# W023X.net
KiCad netlist of a schematic drawn in EAGLE
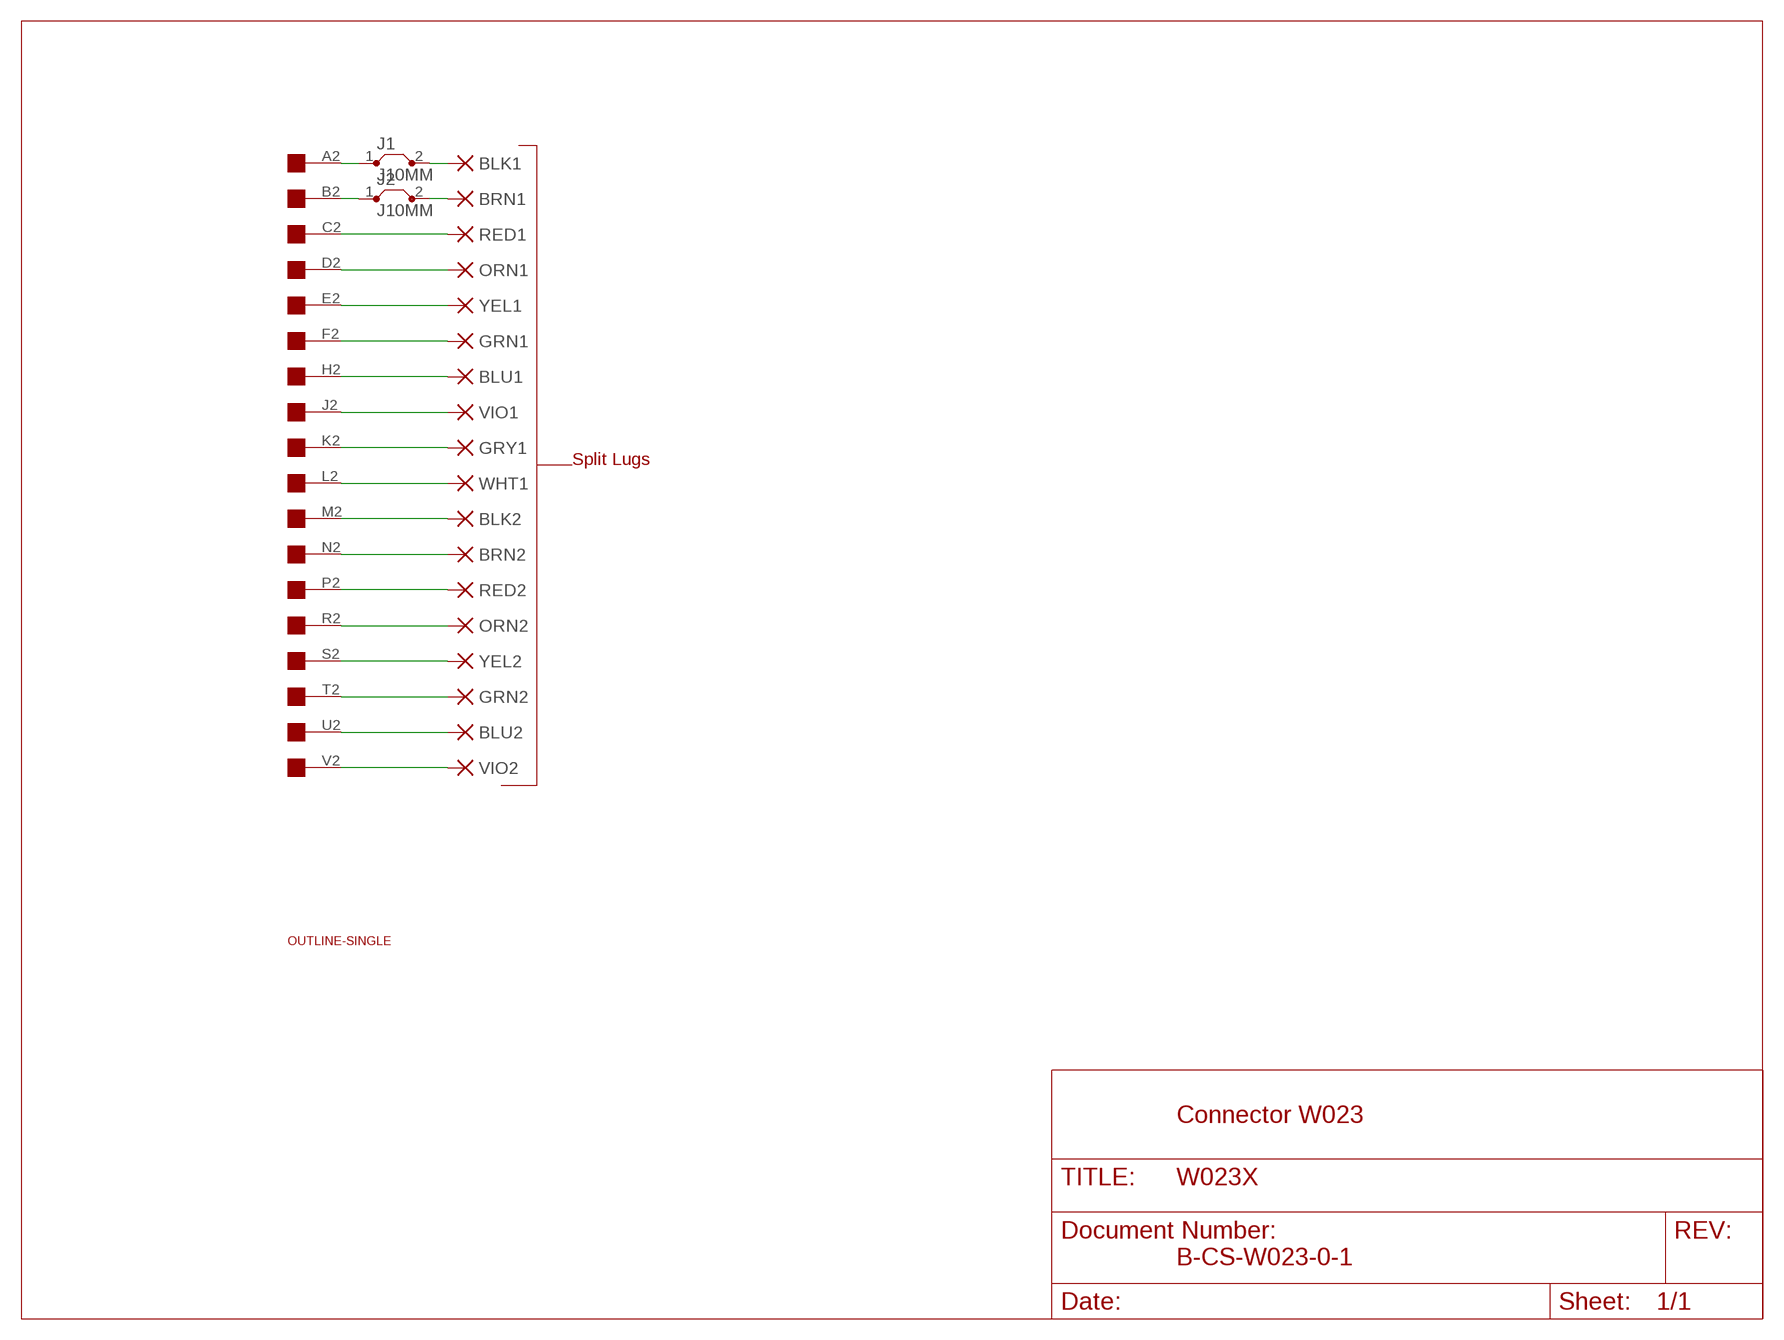
[diagram p0: schematic, sheet 1]

(export (version "E")
  (design (tool "Eeschema 10.0.6"))
  (components
    (comp (ref "BLK1")
      (value "PAD-0465")
      (footprint "eagle-import:0465")
      (libsource (lib "eagle-import") (part "PAD-0465"))
    )
    (comp (ref "BLK2")
      (value "PAD-0465")
      (footprint "eagle-import:0465")
      (libsource (lib "eagle-import") (part "PAD-0465"))
    )
    (comp (ref "BLU1")
      (value "PAD-0465")
      (footprint "eagle-import:0465")
      (libsource (lib "eagle-import") (part "PAD-0465"))
    )
    (comp (ref "BLU2")
      (value "PAD-0465")
      (footprint "eagle-import:0465")
      (libsource (lib "eagle-import") (part "PAD-0465"))
    )
    (comp (ref "BRN1")
      (value "PAD-0465")
      (footprint "eagle-import:0465")
      (libsource (lib "eagle-import") (part "PAD-0465"))
    )
    (comp (ref "BRN2")
      (value "PAD-0465")
      (footprint "eagle-import:0465")
      (libsource (lib "eagle-import") (part "PAD-0465"))
    )
    (comp (ref "GRN1")
      (value "PAD-0465")
      (footprint "eagle-import:0465")
      (libsource (lib "eagle-import") (part "PAD-0465"))
    )
    (comp (ref "GRN2")
      (value "PAD-0465")
      (footprint "eagle-import:0465")
      (libsource (lib "eagle-import") (part "PAD-0465"))
    )
    (comp (ref "GRY1")
      (value "PAD-0465")
      (footprint "eagle-import:0465")
      (libsource (lib "eagle-import") (part "PAD-0465"))
    )
    (comp (ref "J1")
      (value "J10MM")
      (footprint "eagle-import:10")
      (libsource (lib "eagle-import") (part "J10MM"))
    )
    (comp (ref "J2")
      (value "J10MM")
      (footprint "eagle-import:10")
      (libsource (lib "eagle-import") (part "J10MM"))
    )
    (comp (ref "ORN1")
      (value "PAD-0465")
      (footprint "eagle-import:0465")
      (libsource (lib "eagle-import") (part "PAD-0465"))
    )
    (comp (ref "ORN2")
      (value "PAD-0465")
      (footprint "eagle-import:0465")
      (libsource (lib "eagle-import") (part "PAD-0465"))
    )
    (comp (ref "RED1")
      (value "PAD-0465")
      (footprint "eagle-import:0465")
      (libsource (lib "eagle-import") (part "PAD-0465"))
    )
    (comp (ref "RED2")
      (value "PAD-0465")
      (footprint "eagle-import:0465")
      (libsource (lib "eagle-import") (part "PAD-0465"))
    )
    (comp (ref "U$1")
      (value "OUTLINE-SINGLE")
      (footprint "eagle-import:SINGLE")
      (libsource (lib "eagle-import") (part "OUTLINE-SINGLE"))
    )
    (comp (ref "U$2")
      (value "EDGE-1")
      (footprint "eagle-import:EDGE-CON1")
      (libsource (lib "eagle-import") (part "EDGE-1"))
    )
    (comp (ref "VIO1")
      (value "PAD-0465")
      (footprint "eagle-import:0465")
      (libsource (lib "eagle-import") (part "PAD-0465"))
    )
    (comp (ref "VIO2")
      (value "PAD-0465")
      (footprint "eagle-import:0465")
      (libsource (lib "eagle-import") (part "PAD-0465"))
    )
    (comp (ref "WHT1")
      (value "PAD-0465")
      (footprint "eagle-import:0465")
      (libsource (lib "eagle-import") (part "PAD-0465"))
    )
    (comp (ref "YEL1")
      (value "PAD-0465")
      (footprint "eagle-import:0465")
      (libsource (lib "eagle-import") (part "PAD-0465"))
    )
    (comp (ref "YEL2")
      (value "PAD-0465")
      (footprint "eagle-import:0465")
      (libsource (lib "eagle-import") (part "PAD-0465"))
    )
  )
  (nets
    (net (code "1") (name "Net-(BLK1-P)") (class "Default")
      (node (ref "BLK1") (pin "P$1") (pinfunction "P_P$1") (pintype "passive"))
      (node (ref "J1") (pin "2") (pinfunction "2_2") (pintype "passive"))
    )
    (net (code "2") (name "Net-(BLK2-P)") (class "Default")
      (node (ref "BLK2") (pin "P$1") (pinfunction "P_P$1") (pintype "passive"))
      (node (ref "U$2") (pin "M2") (pinfunction "1_M2") (pintype "bidirectional"))
    )
    (net (code "3") (name "Net-(BLU1-P)") (class "Default")
      (node (ref "BLU1") (pin "P$1") (pinfunction "P_P$1") (pintype "passive"))
      (node (ref "U$2") (pin "H2") (pinfunction "1_H2") (pintype "bidirectional"))
    )
    (net (code "4") (name "Net-(BLU2-P)") (class "Default")
      (node (ref "BLU2") (pin "P$1") (pinfunction "P_P$1") (pintype "passive"))
      (node (ref "U$2") (pin "U2") (pinfunction "1_U2") (pintype "bidirectional"))
    )
    (net (code "5") (name "Net-(BRN1-P)") (class "Default")
      (node (ref "BRN1") (pin "P$1") (pinfunction "P_P$1") (pintype "passive"))
      (node (ref "J2") (pin "2") (pinfunction "2_2") (pintype "passive"))
    )
    (net (code "6") (name "Net-(BRN2-P)") (class "Default")
      (node (ref "BRN2") (pin "P$1") (pinfunction "P_P$1") (pintype "passive"))
      (node (ref "U$2") (pin "N2") (pinfunction "1_N2") (pintype "bidirectional"))
    )
    (net (code "7") (name "Net-(GRN1-P)") (class "Default")
      (node (ref "GRN1") (pin "P$1") (pinfunction "P_P$1") (pintype "passive"))
      (node (ref "U$2") (pin "F2") (pinfunction "1_F2") (pintype "bidirectional"))
    )
    (net (code "8") (name "Net-(GRN2-P)") (class "Default")
      (node (ref "GRN2") (pin "P$1") (pinfunction "P_P$1") (pintype "passive"))
      (node (ref "U$2") (pin "T2") (pinfunction "1_T2") (pintype "bidirectional"))
    )
    (net (code "9") (name "Net-(GRY1-P)") (class "Default")
      (node (ref "GRY1") (pin "P$1") (pinfunction "P_P$1") (pintype "passive"))
      (node (ref "U$2") (pin "K2") (pinfunction "1_K2") (pintype "bidirectional"))
    )
    (net (code "10") (name "Net-(ORN1-P)") (class "Default")
      (node (ref "ORN1") (pin "P$1") (pinfunction "P_P$1") (pintype "passive"))
      (node (ref "U$2") (pin "D2") (pinfunction "1_D2") (pintype "bidirectional"))
    )
    (net (code "11") (name "Net-(ORN2-P)") (class "Default")
      (node (ref "ORN2") (pin "P$1") (pinfunction "P_P$1") (pintype "passive"))
      (node (ref "U$2") (pin "R2") (pinfunction "1_R2") (pintype "bidirectional"))
    )
    (net (code "12") (name "Net-(RED1-P)") (class "Default")
      (node (ref "RED1") (pin "P$1") (pinfunction "P_P$1") (pintype "passive"))
      (node (ref "U$2") (pin "C2") (pinfunction "1_C2") (pintype "bidirectional"))
    )
    (net (code "13") (name "Net-(RED2-P)") (class "Default")
      (node (ref "RED2") (pin "P$1") (pinfunction "P_P$1") (pintype "passive"))
      (node (ref "U$2") (pin "P2") (pinfunction "1_P2") (pintype "bidirectional"))
    )
    (net (code "14") (name "Net-(U$2A-1)") (class "Default")
      (node (ref "J1") (pin "1") (pinfunction "1_1") (pintype "passive"))
      (node (ref "U$2") (pin "A2") (pinfunction "1_A2") (pintype "bidirectional"))
    )
    (net (code "15") (name "Net-(U$2B-1)") (class "Default")
      (node (ref "J2") (pin "1") (pinfunction "1_1") (pintype "passive"))
      (node (ref "U$2") (pin "B2") (pinfunction "1_B2") (pintype "bidirectional"))
    )
    (net (code "16") (name "Net-(U$2E-1)") (class "Default")
      (node (ref "U$2") (pin "E2") (pinfunction "1_E2") (pintype "bidirectional"))
      (node (ref "YEL1") (pin "P$1") (pinfunction "P_P$1") (pintype "passive"))
    )
    (net (code "17") (name "Net-(U$2H-1)") (class "Default")
      (node (ref "U$2") (pin "J2") (pinfunction "1_J2") (pintype "bidirectional"))
      (node (ref "VIO1") (pin "P$1") (pinfunction "P_P$1") (pintype "passive"))
    )
    (net (code "18") (name "Net-(U$2J-1)") (class "Default")
      (node (ref "U$2") (pin "L2") (pinfunction "1_L2") (pintype "bidirectional"))
      (node (ref "WHT1") (pin "P$1") (pinfunction "P_P$1") (pintype "passive"))
    )
    (net (code "19") (name "Net-(U$2O-1)") (class "Default")
      (node (ref "U$2") (pin "S2") (pinfunction "1_S2") (pintype "bidirectional"))
      (node (ref "YEL2") (pin "P$1") (pinfunction "P_P$1") (pintype "passive"))
    )
    (net (code "20") (name "Net-(U$2R-1)") (class "Default")
      (node (ref "U$2") (pin "V2") (pinfunction "1_V2") (pintype "bidirectional"))
      (node (ref "VIO2") (pin "P$1") (pinfunction "P_P$1") (pintype "passive"))
    )
  )
)
